# Stepper_Motor4.net
KiCad netlist of a schematic drawn in Altium Designer
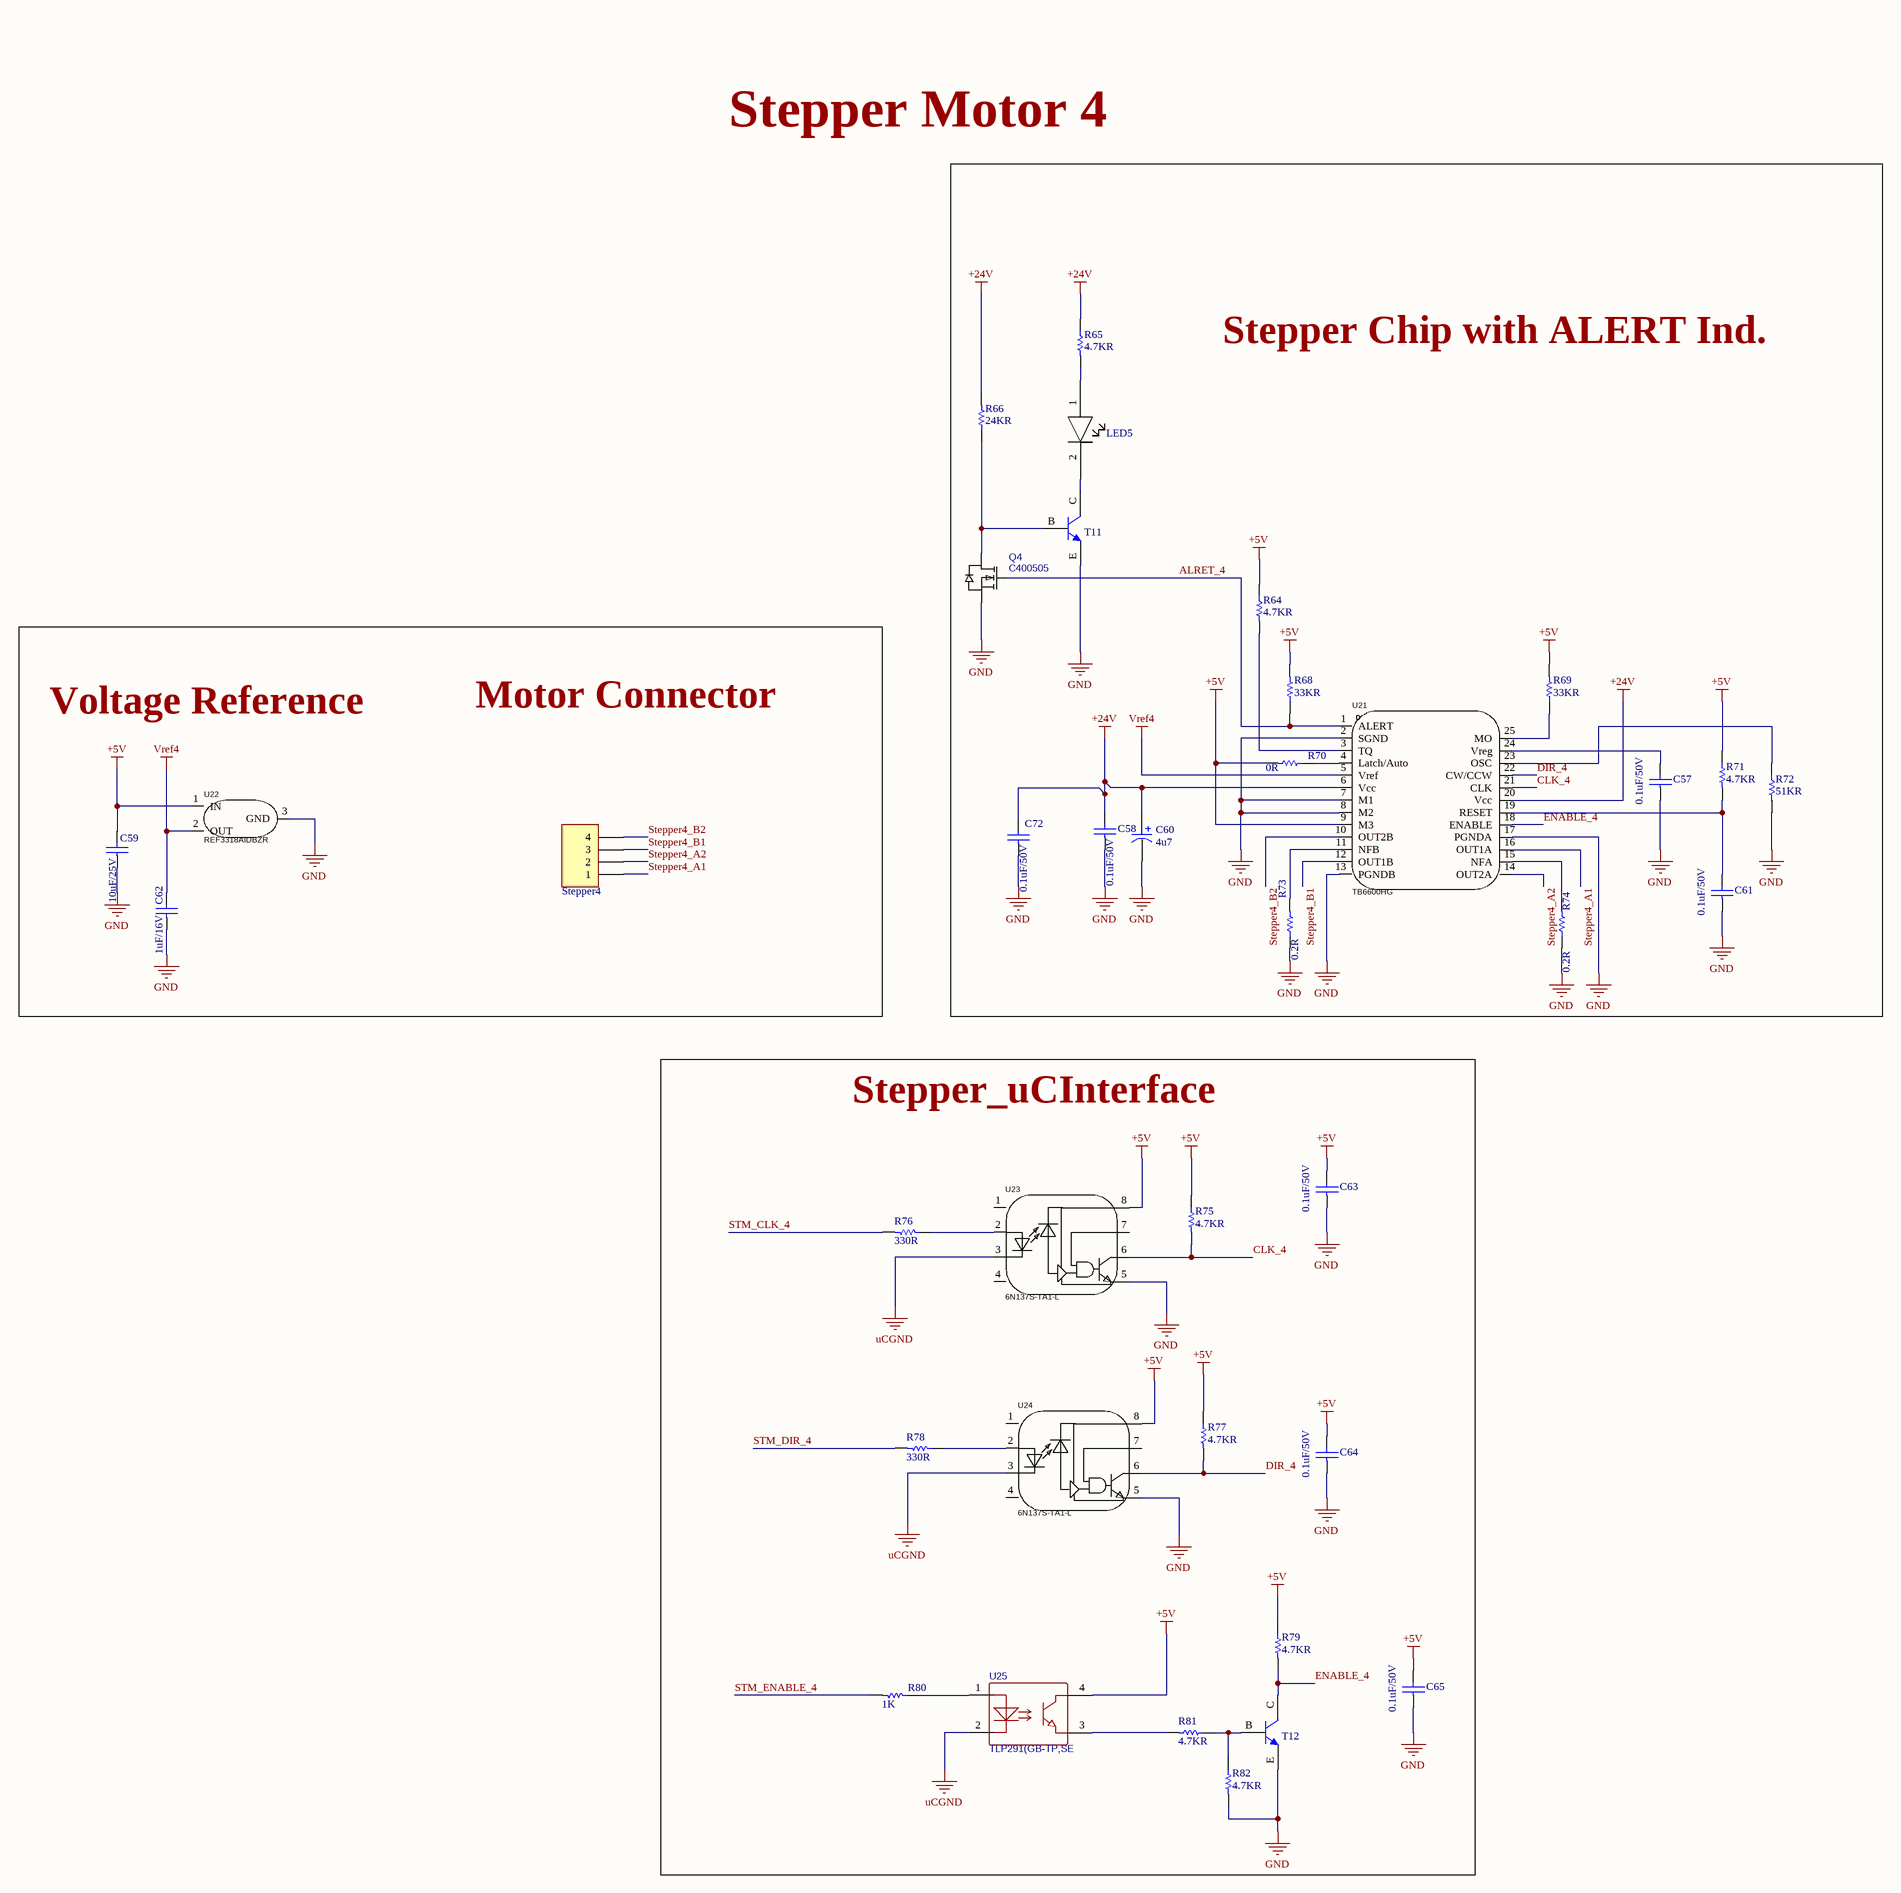
[diagram p0: Stepper Motor4.SchDoc]

(export (version "E")
  (design (tool "Eeschema 10.0.6"))
  (components
    (comp (ref "C57")
      (value "0.1uF/50V")
      (footprint "PCBComponent_1")
      (description "C1591")
      (fields (field (name "CREATED BY") "NourAldin"))
      (libsource (lib "0603 Capacitor") (part "0603 Capacitor"))
    )
    (comp (ref "C58")
      (value "0.1uF/50V")
      (footprint "PCBComponent_1")
      (description "C1591")
      (fields (field (name "CREATED BY") "NourAldin"))
      (libsource (lib "0603 Capacitor") (part "0603 Capacitor"))
    )
    (comp (ref "C59")
      (value "10uF/25V")
      (footprint "PCBComponent_1")
      (description "C96446")
      (fields (field (name "CREATED BY") "NourAldin"))
      (libsource (lib "0603 Capacitor") (part "0603 Capacitor"))
    )
    (comp (ref "C60")
      (value "4u7")
      (footprint "CAPLEAD_D6.3mm")
      (description "C2691843")
      (fields
        (field (name "MANUFACTURER") "KEMET")
        (field (name "MANUFACTURER PART NUMBER") "A759EQ475M2AAAE160")
      )
      (libsource (lib "GlobalLib") (part "A759EQ475M2AAAE160"))
    )
    (comp (ref "C61")
      (value "0.1uF/50V")
      (footprint "PCBComponent_1")
      (description "C1591")
      (fields (field (name "CREATED BY") "NourAldin"))
      (libsource (lib "0603 Capacitor") (part "0603 Capacitor"))
    )
    (comp (ref "C62")
      (value "1uF/16V")
      (footprint "PCBComponent_1")
      (description "C1592")
      (fields (field (name "CREATED BY") "NourAldin"))
      (libsource (lib "0603 Capacitor") (part "0603 Capacitor"))
    )
    (comp (ref "C63")
      (value "0.1uF/50V")
      (footprint "PCBComponent_1")
      (description "C1591")
      (fields (field (name "CREATED BY") "NourAldin"))
      (libsource (lib "0603 Capacitor") (part "0603 Capacitor"))
    )
    (comp (ref "C64")
      (value "0.1uF/50V")
      (footprint "PCBComponent_1")
      (description "C1591")
      (fields (field (name "CREATED BY") "NourAldin"))
      (libsource (lib "0603 Capacitor") (part "0603 Capacitor"))
    )
    (comp (ref "C65")
      (value "0.1uF/50V")
      (footprint "PCBComponent_1")
      (description "C1591")
      (fields (field (name "CREATED BY") "NourAldin"))
      (libsource (lib "0603 Capacitor") (part "0603 Capacitor"))
    )
    (comp (ref "C72")
      (value "0.1uF/50V")
      (footprint "PCBComponent_1")
      (description "C1591")
      (fields (field (name "CREATED BY") "NourAldin"))
      (libsource (lib "0603 Capacitor") (part "0603 Capacitor"))
    )
    (comp (ref "LED5")
      (value "1206 LED")
      (footprint "1206 LED")
      (description "C434438")
      (fields (field (name "CREATED BY") "NourAldin"))
      (libsource (lib "1206 LED") (part "1206 LED"))
    )
    (comp (ref "Q4")
      (value "C400505")
      (footprint "SOT-23-3_L2.9-W1.3-P1.90-LS2.4-BR")
      (fields
        (field (name "MANUFACTURER") "YANGJIE(扬杰)")
        (field (name "MANUFACTURER PART") "BSS138")
        (field (name "CONTRIBUTOR") "LCSC")
      )
      (libsource (lib "DIVERSE") (part "BSS138_MOSFET"))
    )
    (comp (ref "R64")
      (value "4.7KR")
      (footprint "R0402")
      (description "C105871")
      (libsource (lib "DIVERSE") (part "0402 Resistor"))
    )
    (comp (ref "R65")
      (value "4.7KR")
      (footprint "R0402")
      (description "C105871")
      (libsource (lib "DIVERSE") (part "0402 Resistor"))
    )
    (comp (ref "R66")
      (value "24KR")
      (footprint "RESC1608X06N")
      (description "C2930081")
      (fields (field (name "CREATED BY") "NourAldin"))
      (libsource (lib "0603 Resistor") (part "0603 Resistor"))
    )
    (comp (ref "R68")
      (value "33KR")
      (footprint "RESC1608X06N")
      (description "C126359")
      (fields (field (name "CREATED BY") "NourAldin"))
      (libsource (lib "0603 Resistor") (part "0603 Resistor"))
    )
    (comp (ref "R69")
      (value "33KR")
      (footprint "RESC1608X06N")
      (description "C126359")
      (fields (field (name "CREATED BY") "NourAldin"))
      (libsource (lib "0603 Resistor") (part "0603 Resistor"))
    )
    (comp (ref "R70")
      (value "0R")
      (footprint "RESC1608X06N")
      (description "C100044")
      (fields (field (name "CREATED BY") "NourAldin"))
      (libsource (lib "0603 Resistor") (part "0603 Resistor"))
    )
    (comp (ref "R71")
      (value "4.7KR")
      (footprint "R0402")
      (description "C105871")
      (libsource (lib "DIVERSE") (part "0402 Resistor"))
    )
    (comp (ref "R72")
      (value "51KR")
      (footprint "R0402")
      (description "C107230")
      (libsource (lib "DIVERSE") (part "0402 Resistor"))
    )
    (comp (ref "R73")
      (value "0.2R")
      (footprint "RESC6431X12N")
      (description "C2903473")
      (fields (field (name "CREATED BY") "NourAldin"))
      (libsource (lib "2512 Resistor") (part "2512 Resistor"))
    )
    (comp (ref "R74")
      (value "0.2R")
      (footprint "RESC6431X12N")
      (description "C2903473")
      (fields (field (name "CREATED BY") "NourAldin"))
      (libsource (lib "2512 Resistor") (part "2512 Resistor"))
    )
    (comp (ref "R75")
      (value "4.7KR")
      (footprint "R0402")
      (description "C105871")
      (libsource (lib "DIVERSE") (part "0402 Resistor"))
    )
    (comp (ref "R76")
      (value "330R")
      (footprint "R0402")
      (description "C105875")
      (libsource (lib "DIVERSE") (part "0402 Resistor"))
    )
    (comp (ref "R77")
      (value "4.7KR")
      (footprint "R0402")
      (description "C105871")
      (libsource (lib "DIVERSE") (part "0402 Resistor"))
    )
    (comp (ref "R78")
      (value "330R")
      (footprint "R0402")
      (description "C105875")
      (libsource (lib "DIVERSE") (part "0402 Resistor"))
    )
    (comp (ref "R79")
      (value "4.7KR")
      (footprint "R0402")
      (description "C105871")
      (libsource (lib "DIVERSE") (part "0402 Resistor"))
    )
    (comp (ref "R80")
      (value "1K")
      (footprint "R0402")
      (description "C106235")
      (libsource (lib "DIVERSE") (part "0402 Resistor"))
    )
    (comp (ref "R81")
      (value "4.7KR")
      (footprint "R0402")
      (description "C105871")
      (libsource (lib "DIVERSE") (part "0402 Resistor"))
    )
    (comp (ref "R82")
      (value "4.7KR")
      (footprint "R0402")
      (description "C105871")
      (libsource (lib "DIVERSE") (part "0402 Resistor"))
    )
    (comp (ref "Stepper4")
      (value "Header 4 Pin Polar")
      (footprint "PCBComponent_1")
      (description "C144395")
      (libsource (lib "Header 4 Pin Polar") (part "Header 4 Pin Polar"))
    )
    (comp (ref "T11")
      (value "MMBT3904 Transistor")
      (footprint "MMBT3904")
      (description "C108429")
      (fields (field (name "CREATED BY") "NourAldin"))
      (libsource (lib "MMBT3904 Transistor") (part "MMBT3904 Transistor"))
    )
    (comp (ref "T12")
      (value "MMBT3904 Transistor")
      (footprint "MMBT3904")
      (description "C108429")
      (fields (field (name "CREATED BY") "NourAldin"))
      (libsource (lib "MMBT3904 Transistor") (part "MMBT3904 Transistor"))
    )
    (comp (ref "U21")
      (value "TB6600HG")
      (footprint "HZIP25-P-1.0_TB6600HG - HEATSINK")
      (description "C66042")
      (fields (field (name "MANUFACTURER") "TOSHIBA(东芝)"))
      (libsource (lib "LIB") (part "TB6600HG"))
    )
    (comp (ref "U22")
      (value "REF3318AIDBZR")
      (footprint "SOT-23-3_L2.9-W1.3-P1.90-LS2.4-BR")
      (description "C115877")
      (fields (field (name "MANUFACTURER") "TI(德州仪器)") (field (name "TOLERANCE") "±0.15%"))
      (libsource (lib "LIB") (part "REF3318AIDBZR"))
    )
    (comp (ref "U23")
      (value "6N137S-TA1-L")
      (footprint "SOP-8_L9.8-W6.6-P2.54-LS10.3-BL")
      (description "C92651")
      (fields (field (name "MANUFACTURER") "LITEON(光宝)"))
      (libsource (lib "LIB") (part "6N137S-TA1-L"))
    )
    (comp (ref "U24")
      (value "6N137S-TA1-L")
      (footprint "SOP-8_L9.8-W6.6-P2.54-LS10.3-BL")
      (description "C92651")
      (fields (field (name "MANUFACTURER") "LITEON(光宝)"))
      (libsource (lib "LIB") (part "6N137S-TA1-L"))
    )
    (comp (ref "U25")
      (value "TLP291(GB-TP,SE")
      (footprint "SOP-4-1.27mm")
      (description "C55144")
      (libsource (lib "CO2_Lib") (part "TLP291(GB-TP,SE(T"))
    )
  )
  (nets
    (net (code "1") (name "+5V") (class "Default")
      (node (ref "C59") (pin "2") (pinfunction "2_2") (pintype "passive"))
      (node (ref "C63") (pin "2") (pinfunction "2_2") (pintype "passive"))
      (node (ref "C64") (pin "2") (pinfunction "2_2") (pintype "passive"))
      (node (ref "C65") (pin "2") (pinfunction "2_2") (pintype "passive"))
      (node (ref "R64") (pin "1") (pinfunction "1_1") (pintype "passive"))
      (node (ref "R68") (pin "2") (pinfunction "2_2") (pintype "passive"))
      (node (ref "R69") (pin "2") (pinfunction "2_2") (pintype "passive"))
      (node (ref "R70") (pin "2") (pinfunction "2_2") (pintype "passive"))
      (node (ref "R71") (pin "1") (pinfunction "1_1") (pintype "passive"))
      (node (ref "R75") (pin "1") (pinfunction "1_1") (pintype "passive"))
      (node (ref "R77") (pin "1") (pinfunction "1_1") (pintype "passive"))
      (node (ref "R79") (pin "1") (pinfunction "1_1") (pintype "passive"))
      (node (ref "U21") (pin "9") (pinfunction "M3_9") (pintype "passive"))
      (node (ref "U22") (pin "1") (pinfunction "IN_1") (pintype "passive"))
      (node (ref "U23") (pin "8") (pinfunction "8_8") (pintype "passive"))
      (node (ref "U24") (pin "8") (pinfunction "8_8") (pintype "passive"))
      (node (ref "U25") (pin "4") (pinfunction "4_4") (pintype "passive"))
    )
    (net (code "2") (name "+24V") (class "Default")
      (node (ref "C58") (pin "2") (pinfunction "2_2") (pintype "passive"))
      (node (ref "C60") (pin "1") (pinfunction "1_1") (pintype "passive"))
      (node (ref "C72") (pin "2") (pinfunction "2_2") (pintype "passive"))
      (node (ref "R65") (pin "1") (pinfunction "1_1") (pintype "passive"))
      (node (ref "R66") (pin "2") (pinfunction "2_2") (pintype "passive"))
      (node (ref "U21") (pin "20") (pinfunction "Vcc_20") (pintype "passive"))
      (node (ref "U21") (pin "6") (pinfunction "Vcc_6") (pintype "passive"))
    )
    (net (code "3") (name "/ALRET_4") (class "Default")
      (node (ref "Q4") (pin "1") (pinfunction "G_1") (pintype "passive"))
      (node (ref "R68") (pin "1") (pinfunction "1_1") (pintype "passive"))
      (node (ref "U21") (pin "1") (pinfunction "ALERT_1") (pintype "passive"))
    )
    (net (code "4") (name "/CLK_4") (class "Default")
      (node (ref "R75") (pin "2") (pinfunction "2_2") (pintype "passive"))
      (node (ref "U21") (pin "21") (pinfunction "CLK_21") (pintype "passive"))
      (node (ref "U23") (pin "6") (pinfunction "6_6") (pintype "passive"))
    )
    (net (code "5") (name "/DIR_4") (class "Default")
      (node (ref "R77") (pin "2") (pinfunction "2_2") (pintype "passive"))
      (node (ref "U21") (pin "22") (pinfunction "CW/CCW_22") (pintype "passive"))
      (node (ref "U24") (pin "6") (pinfunction "6_6") (pintype "passive"))
    )
    (net (code "6") (name "/ENABLE_4") (class "Default")
      (node (ref "R79") (pin "2") (pinfunction "2_2") (pintype "passive"))
      (node (ref "T12") (pin "C") (pinfunction "C_C") (pintype "passive"))
      (node (ref "U21") (pin "18") (pinfunction "ENABLE_18") (pintype "passive"))
    )
    (net (code "7") (name "/STM_CLK_4") (class "Default")
      (node (ref "R76") (pin "2") (pinfunction "2_2") (pintype "passive"))
    )
    (net (code "8") (name "/STM_DIR_4") (class "Default")
      (node (ref "R78") (pin "2") (pinfunction "2_2") (pintype "passive"))
    )
    (net (code "9") (name "/STM_ENABLE_4") (class "Default")
      (node (ref "R80") (pin "2") (pinfunction "2_2") (pintype "passive"))
    )
    (net (code "10") (name "/Stepper4_A1") (class "Default")
      (node (ref "Stepper4") (pin "1") (pinfunction "1_1") (pintype "passive"))
      (node (ref "U21") (pin "16") (pinfunction "OUT1A_16") (pintype "passive"))
    )
    (net (code "11") (name "/Stepper4_A2") (class "Default")
      (node (ref "Stepper4") (pin "2") (pinfunction "2_2") (pintype "passive"))
      (node (ref "U21") (pin "14") (pinfunction "OUT2A_14") (pintype "passive"))
    )
    (net (code "12") (name "/Stepper4_B1") (class "Default")
      (node (ref "Stepper4") (pin "3") (pinfunction "3_3") (pintype "passive"))
      (node (ref "U21") (pin "12") (pinfunction "OUT1B_12") (pintype "passive"))
    )
    (net (code "13") (name "/Stepper4_B2") (class "Default")
      (node (ref "Stepper4") (pin "4") (pinfunction "4_4") (pintype "passive"))
      (node (ref "U21") (pin "10") (pinfunction "OUT2B_10") (pintype "passive"))
    )
    (net (code "14") (name "GND") (class "Default")
      (node (ref "C57") (pin "1") (pinfunction "1_1") (pintype "passive"))
      (node (ref "C58") (pin "1") (pinfunction "1_1") (pintype "passive"))
      (node (ref "C59") (pin "1") (pinfunction "1_1") (pintype "passive"))
      (node (ref "C60") (pin "2") (pinfunction "2_2") (pintype "passive"))
      (node (ref "C61") (pin "1") (pinfunction "1_1") (pintype "passive"))
      (node (ref "C62") (pin "1") (pinfunction "1_1") (pintype "passive"))
      (node (ref "C63") (pin "1") (pinfunction "1_1") (pintype "passive"))
      (node (ref "C64") (pin "1") (pinfunction "1_1") (pintype "passive"))
      (node (ref "C65") (pin "1") (pinfunction "1_1") (pintype "passive"))
      (node (ref "C72") (pin "1") (pinfunction "1_1") (pintype "passive"))
      (node (ref "Q4") (pin "2") (pinfunction "S_2") (pintype "passive"))
      (node (ref "R72") (pin "2") (pinfunction "2_2") (pintype "passive"))
      (node (ref "R73") (pin "1") (pinfunction "1_1") (pintype "passive"))
      (node (ref "R74") (pin "1") (pinfunction "1_1") (pintype "passive"))
      (node (ref "R82") (pin "2") (pinfunction "2_2") (pintype "passive"))
      (node (ref "T11") (pin "E") (pinfunction "E_E") (pintype "passive"))
      (node (ref "T12") (pin "E") (pinfunction "E_E") (pintype "passive"))
      (node (ref "U21") (pin "13") (pinfunction "PGNDB_13") (pintype "passive"))
      (node (ref "U21") (pin "17") (pinfunction "PGNDA_17") (pintype "passive"))
      (node (ref "U21") (pin "2") (pinfunction "SGND_2") (pintype "passive"))
      (node (ref "U21") (pin "7") (pinfunction "M1_7") (pintype "passive"))
      (node (ref "U21") (pin "8") (pinfunction "M2_8") (pintype "passive"))
      (node (ref "U22") (pin "3") (pinfunction "GND_3") (pintype "passive"))
      (node (ref "U23") (pin "5") (pinfunction "5_5") (pintype "passive"))
      (node (ref "U24") (pin "5") (pinfunction "5_5") (pintype "passive"))
    )
    (net (code "15") (name "Net-(LED5-Pad1)") (class "Default")
      (node (ref "LED5") (pin "1") (pinfunction "1_1") (pintype "passive"))
      (node (ref "R65") (pin "2") (pinfunction "2_2") (pintype "passive"))
    )
    (net (code "16") (name "Net-(LED5-Pad2)") (class "Default")
      (node (ref "LED5") (pin "2") (pinfunction "2_2") (pintype "passive"))
      (node (ref "T11") (pin "C") (pinfunction "C_C") (pintype "passive"))
    )
    (net (code "17") (name "Net-(Q4-D)") (class "Default")
      (node (ref "Q4") (pin "3") (pinfunction "D_3") (pintype "passive"))
      (node (ref "R66") (pin "1") (pinfunction "1_1") (pintype "passive"))
      (node (ref "T11") (pin "B") (pinfunction "B_B") (pintype "passive"))
    )
    (net (code "18") (name "Net-(R76-Pad1)") (class "Default")
      (node (ref "R76") (pin "1") (pinfunction "1_1") (pintype "passive"))
      (node (ref "U23") (pin "2") (pinfunction "2_2") (pintype "passive"))
    )
    (net (code "19") (name "Net-(R78-Pad1)") (class "Default")
      (node (ref "R78") (pin "1") (pinfunction "1_1") (pintype "passive"))
      (node (ref "U24") (pin "2") (pinfunction "2_2") (pintype "passive"))
    )
    (net (code "20") (name "Net-(R80-Pad1)") (class "Default")
      (node (ref "R80") (pin "1") (pinfunction "1_1") (pintype "passive"))
      (node (ref "U25") (pin "1") (pinfunction "1_1") (pintype "passive"))
    )
    (net (code "21") (name "Net-(R81-Pad1)") (class "Default")
      (node (ref "R81") (pin "1") (pinfunction "1_1") (pintype "passive"))
      (node (ref "R82") (pin "1") (pinfunction "1_1") (pintype "passive"))
      (node (ref "T12") (pin "B") (pinfunction "B_B") (pintype "passive"))
    )
    (net (code "22") (name "Net-(R81-Pad2)") (class "Default")
      (node (ref "R81") (pin "2") (pinfunction "2_2") (pintype "passive"))
      (node (ref "U25") (pin "3") (pinfunction "3_3") (pintype "passive"))
    )
    (net (code "23") (name "Net-(U21-Latch{slash}Auto)") (class "Default")
      (node (ref "R70") (pin "1") (pinfunction "1_1") (pintype "passive"))
      (node (ref "U21") (pin "4") (pinfunction "Latch/Auto_4") (pintype "passive"))
    )
    (net (code "24") (name "Net-(U21-MO)") (class "Default")
      (node (ref "R69") (pin "1") (pinfunction "1_1") (pintype "passive"))
      (node (ref "U21") (pin "25") (pinfunction "MO_25") (pintype "passive"))
    )
    (net (code "25") (name "Net-(U21-NFA)") (class "Default")
      (node (ref "R74") (pin "2") (pinfunction "2_2") (pintype "passive"))
      (node (ref "U21") (pin "15") (pinfunction "NFA_15") (pintype "passive"))
    )
    (net (code "26") (name "Net-(U21-NFB)") (class "Default")
      (node (ref "R73") (pin "2") (pinfunction "2_2") (pintype "passive"))
      (node (ref "U21") (pin "11") (pinfunction "NFB_11") (pintype "passive"))
    )
    (net (code "27") (name "Net-(U21-OSC)") (class "Default")
      (node (ref "R72") (pin "1") (pinfunction "1_1") (pintype "passive"))
      (node (ref "U21") (pin "23") (pinfunction "OSC_23") (pintype "passive"))
    )
    (net (code "28") (name "Net-(U21-RESET)") (class "Default")
      (node (ref "C61") (pin "2") (pinfunction "2_2") (pintype "passive"))
      (node (ref "R71") (pin "2") (pinfunction "2_2") (pintype "passive"))
      (node (ref "U21") (pin "19") (pinfunction "RESET_19") (pintype "passive"))
    )
    (net (code "29") (name "Net-(U21-TQ)") (class "Default")
      (node (ref "R64") (pin "2") (pinfunction "2_2") (pintype "passive"))
      (node (ref "U21") (pin "3") (pinfunction "TQ_3") (pintype "passive"))
    )
    (net (code "30") (name "Net-(U21-Vreg)") (class "Default")
      (node (ref "C57") (pin "2") (pinfunction "2_2") (pintype "passive"))
      (node (ref "U21") (pin "24") (pinfunction "Vreg_24") (pintype "passive"))
    )
    (net (code "31") (name "Vref4") (class "Default")
      (node (ref "C62") (pin "2") (pinfunction "2_2") (pintype "passive"))
      (node (ref "U21") (pin "5") (pinfunction "Vref_5") (pintype "passive"))
      (node (ref "U22") (pin "2") (pinfunction "OUT_2") (pintype "passive"))
    )
    (net (code "32") (name "uCGND") (class "Default")
      (node (ref "U23") (pin "3") (pinfunction "3_3") (pintype "passive"))
      (node (ref "U24") (pin "3") (pinfunction "3_3") (pintype "passive"))
      (node (ref "U25") (pin "2") (pinfunction "2_2") (pintype "passive"))
    )
    (net (code "33") (name "unconnected-(U23-NC-Pad1)") (class "Default")
      (node (ref "U23") (pin "1") (pinfunction "NC_1") (pintype "passive"))
    )
    (net (code "34") (name "unconnected-(U23-NC-Pad4)") (class "Default")
      (node (ref "U23") (pin "4") (pinfunction "NC_4") (pintype "passive"))
    )
    (net (code "35") (name "unconnected-(U23-Pad7)") (class "Default")
      (node (ref "U23") (pin "7") (pinfunction "7_7") (pintype "passive"))
    )
    (net (code "36") (name "unconnected-(U24-NC-Pad1)") (class "Default")
      (node (ref "U24") (pin "1") (pinfunction "NC_1") (pintype "passive"))
    )
    (net (code "37") (name "unconnected-(U24-NC-Pad4)") (class "Default")
      (node (ref "U24") (pin "4") (pinfunction "NC_4") (pintype "passive"))
    )
    (net (code "38") (name "unconnected-(U24-Pad7)") (class "Default")
      (node (ref "U24") (pin "7") (pinfunction "7_7") (pintype "passive"))
    )
  )
)
